# io_power.net
KiCad netlist of a schematic drawn in Altium Designer
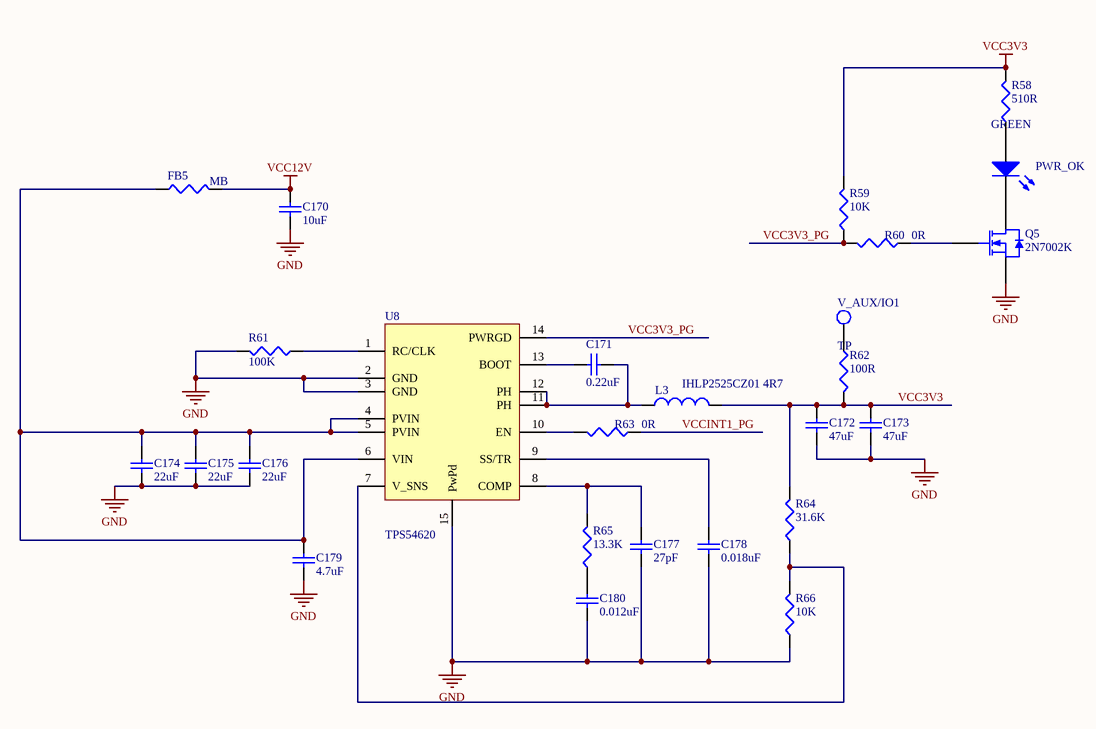
[diagram p0: io_power.SchDoc]

(export (version "E")
  (design (tool "Eeschema 10.0.6"))
  (components
    (comp (ref "C170")
      (value "10uF")
      (footprint "CAPC3216N")
      (description "Capacitor (Semiconductor SIM Model)")
      (fields (field (name "PUBLISHER") "Altium Limited"))
      (libsource (lib "Miscellaneous Devices") (part "Cap Semi"))
    )
    (comp (ref "C171")
      (value "0.22uF")
      (footprint "CAPC1608N")
      (description "Ceramic Chip Capacitor - Standard")
      (fields (field (name "PUBLISHER") "Altium Limited"))
      (libsource (lib "KEMET Chip Capacitor") (part "C0603"))
    )
    (comp (ref "C172")
      (value "47uF")
      (footprint "CAPC3225N")
      (description "Ceramic Chip Capacitor - Standard")
      (fields (field (name "PUBLISHER") "Altium Limited"))
      (libsource (lib "KEMET Chip Capacitor") (part "C1210"))
    )
    (comp (ref "C173")
      (value "47uF")
      (footprint "CAPC3225N")
      (description "Ceramic Chip Capacitor - Standard")
      (fields (field (name "PUBLISHER") "Altium Limited"))
      (libsource (lib "KEMET Chip Capacitor") (part "C1210"))
    )
    (comp (ref "C174")
      (value "22uF")
      (footprint "CAPC3225N")
      (description "Ceramic Chip Capacitor - Standard")
      (fields (field (name "PUBLISHER") "Altium Limited"))
      (libsource (lib "KEMET Chip Capacitor") (part "C1210"))
    )
    (comp (ref "C175")
      (value "22uF")
      (footprint "CAPC3225N")
      (description "Ceramic Chip Capacitor - Standard")
      (fields (field (name "PUBLISHER") "Altium Limited"))
      (libsource (lib "KEMET Chip Capacitor") (part "C1210"))
    )
    (comp (ref "C176")
      (value "22uF")
      (footprint "CAPC3225N")
      (description "Ceramic Chip Capacitor - Standard")
      (fields (field (name "PUBLISHER") "Altium Limited"))
      (libsource (lib "KEMET Chip Capacitor") (part "C1210"))
    )
    (comp (ref "C177")
      (value "27pF")
      (footprint "CAPC1608N")
      (description "Ceramic Chip Capacitor - Standard")
      (fields (field (name "PUBLISHER") "Altium Limited"))
      (libsource (lib "KEMET Chip Capacitor") (part "C0603"))
    )
    (comp (ref "C178")
      (value "0.018uF")
      (footprint "CAPC1608N")
      (description "Ceramic Chip Capacitor - Standard")
      (fields (field (name "PUBLISHER") "Altium Limited"))
      (libsource (lib "KEMET Chip Capacitor") (part "C0603"))
    )
    (comp (ref "C179")
      (value "4.7uF")
      (footprint "CAPC2012N")
      (description "Ceramic Chip Capacitor - Standard")
      (fields (field (name "PUBLISHER") "Altium Limited"))
      (libsource (lib "KEMET Chip Capacitor") (part "C0805"))
    )
    (comp (ref "C180")
      (value "0.012uF")
      (footprint "CAPC1608N")
      (description "Ceramic Chip Capacitor - Standard")
      (fields (field (name "PUBLISHER") "Altium Limited"))
      (libsource (lib "KEMET Chip Capacitor") (part "C0603"))
    )
    (comp (ref "FB5")
      (value "MB")
      (footprint "INDC3216N")
      (description "Resistor")
      (fields (field (name "PUBLISHER") "Altium Limited"))
      (libsource (lib "Miscellaneous Devices") (part "Res3"))
    )
    (comp (ref "L3")
      (value "IHLP2525CZ01")
      (footprint "IHLP2525")
      (description "Inductor")
      (fields (field (name "ALTIUM_VALUE") "4R7") (field (name "PUBLISHER") "Altium Limited"))
      (libsource (lib "S6_2") (part "Inductor"))
    )
    (comp (ref "PWR_OK")
      (value "GREEN")
      (footprint "CD1608-0603")
      (description "Typical BLUE SiC LED")
      (fields (field (name "PUBLISHER") "Altium Limited"))
      (libsource (lib "Miscellaneous Devices") (part "LED3"))
    )
    (comp (ref "Q5")
      (value "2N7002K")
      (footprint "SOT23_N")
      (description "N-channel Enhancement Mode Field-effect Transistor")
      (fields (field (name "PUBLISHER") "Altium Limited"))
      (libsource (lib "Philips Discrete MOSFET - Low Power") (part "2N7002"))
    )
    (comp (ref "R58")
      (value "510R")
      (footprint "RESC1005N")
      (description "Resistor")
      (fields (field (name "PUBLISHER") "Altium Limited"))
      (libsource (lib "Miscellaneous Devices") (part "Res3"))
    )
    (comp (ref "R59")
      (value "10K")
      (footprint "RESC1608N")
      (description "Resistor")
      (fields (field (name "PUBLISHER") "Altium Limited"))
      (libsource (lib "Miscellaneous Devices") (part "Res3"))
    )
    (comp (ref "R60")
      (value "0R")
      (footprint "RESC1005N")
      (description "Resistor")
      (fields (field (name "PUBLISHER") "Altium Limited"))
      (libsource (lib "Miscellaneous Devices") (part "Res3"))
    )
    (comp (ref "R61")
      (value "100K")
      (footprint "RESC1005N")
      (description "Resistor")
      (fields (field (name "PUBLISHER") "Altium Limited"))
      (libsource (lib "Miscellaneous Devices") (part "Res3"))
    )
    (comp (ref "R62")
      (value "100R")
      (footprint "RESC1005N")
      (description "Resistor")
      (fields (field (name "PUBLISHER") "Altium Limited"))
      (libsource (lib "Miscellaneous Devices") (part "Res3"))
    )
    (comp (ref "R63")
      (value "0R")
      (footprint "RESC1005N")
      (description "Resistor")
      (fields (field (name "PUBLISHER") "Altium Limited"))
      (libsource (lib "Miscellaneous Devices") (part "Res3"))
    )
    (comp (ref "R64")
      (value "31.6K")
      (footprint "RESC1608N")
      (description "Resistor")
      (fields (field (name "PUBLISHER") "Altium Limited"))
      (libsource (lib "Miscellaneous Devices") (part "Res3"))
    )
    (comp (ref "R65")
      (value "13.3K")
      (footprint "RESC1608N")
      (description "Resistor")
      (fields (field (name "PUBLISHER") "Altium Limited"))
      (libsource (lib "Miscellaneous Devices") (part "Res3"))
    )
    (comp (ref "R66")
      (value "10K")
      (footprint "RESC1608N")
      (description "Resistor")
      (fields (field (name "PUBLISHER") "Altium Limited"))
      (libsource (lib "Miscellaneous Devices") (part "Res3"))
    )
    (comp (ref "U8") (value "TPS54620") (footprint "VQFN-14") (libsource (lib "S6_2") (part "TPS54620")))
    (comp (ref "V_AUX/IO1") (value "TP") (footprint "PIN1") (libsource (lib "S6") (part "TP")))
  )
  (nets
    (net (code "1") (name "/VCC3V3_PG") (class "Default")
      (node (ref "R59") (pin "1") (pinfunction "1_1") (pintype "passive"))
      (node (ref "R60") (pin "2") (pinfunction "2_2") (pintype "passive"))
      (node (ref "U8") (pin "14") (pinfunction "PWRGD_14") (pintype "passive"))
    )
    (net (code "2") (name "/VCCINT1_PG") (class "Default")
      (node (ref "R63") (pin "1") (pinfunction "1_1") (pintype "passive"))
    )
    (net (code "3") (name "GND") (class "Default")
      (node (ref "C170") (pin "1") (pinfunction "1_1") (pintype "passive"))
      (node (ref "C172") (pin "1") (pinfunction "1_1") (pintype "passive"))
      (node (ref "C173") (pin "1") (pinfunction "1_1") (pintype "passive"))
      (node (ref "C174") (pin "1") (pinfunction "1_1") (pintype "passive"))
      (node (ref "C175") (pin "1") (pinfunction "1_1") (pintype "passive"))
      (node (ref "C176") (pin "1") (pinfunction "1_1") (pintype "passive"))
      (node (ref "C177") (pin "1") (pinfunction "1_1") (pintype "passive"))
      (node (ref "C178") (pin "1") (pinfunction "1_1") (pintype "passive"))
      (node (ref "C179") (pin "1") (pinfunction "1_1") (pintype "passive"))
      (node (ref "C180") (pin "1") (pinfunction "1_1") (pintype "passive"))
      (node (ref "Q5") (pin "2") (pinfunction "S_2") (pintype "passive"))
      (node (ref "R61") (pin "2") (pinfunction "2_2") (pintype "passive"))
      (node (ref "R66") (pin "1") (pinfunction "1_1") (pintype "passive"))
      (node (ref "U8") (pin "15") (pinfunction "PwPd_15") (pintype "passive"))
      (node (ref "U8") (pin "2") (pinfunction "GND_2") (pintype "passive"))
      (node (ref "U8") (pin "3") (pinfunction "GND_3") (pintype "passive"))
    )
    (net (code "4") (name "Net-(C171-Pad2)") (class "Default")
      (node (ref "C171") (pin "2") (pinfunction "2_2") (pintype "passive"))
      (node (ref "L3") (pin "1") (pinfunction "1_1") (pintype "passive"))
      (node (ref "U8") (pin "11") (pinfunction "PH_11") (pintype "passive"))
      (node (ref "U8") (pin "12") (pinfunction "PH_12") (pintype "passive"))
    )
    (net (code "5") (name "Net-(C180-Pad2)") (class "Default")
      (node (ref "C180") (pin "2") (pinfunction "2_2") (pintype "passive"))
      (node (ref "R65") (pin "1") (pinfunction "1_1") (pintype "passive"))
    )
    (net (code "6") (name "Net-(PWR_OK-A)") (class "Default")
      (node (ref "PWR_OK") (pin "1") (pinfunction "A_1") (pintype "passive"))
      (node (ref "R58") (pin "1") (pinfunction "1_1") (pintype "passive"))
    )
    (net (code "7") (name "Net-(PWR_OK-K)") (class "Default")
      (node (ref "PWR_OK") (pin "2") (pinfunction "K_2") (pintype "passive"))
      (node (ref "Q5") (pin "3") (pinfunction "D_3") (pintype "passive"))
    )
    (net (code "8") (name "Net-(Q5-G)") (class "Default")
      (node (ref "Q5") (pin "1") (pinfunction "G_1") (pintype "passive"))
      (node (ref "R60") (pin "1") (pinfunction "1_1") (pintype "passive"))
    )
    (net (code "9") (name "Net-(U8-BOOT)") (class "Default")
      (node (ref "C171") (pin "1") (pinfunction "1_1") (pintype "passive"))
      (node (ref "U8") (pin "13") (pinfunction "BOOT_13") (pintype "passive"))
    )
    (net (code "10") (name "Net-(U8-COMP)") (class "Default")
      (node (ref "C177") (pin "2") (pinfunction "2_2") (pintype "passive"))
      (node (ref "R65") (pin "2") (pinfunction "2_2") (pintype "passive"))
      (node (ref "U8") (pin "8") (pinfunction "COMP_8") (pintype "passive"))
    )
    (net (code "11") (name "Net-(U8-EN)") (class "Default")
      (node (ref "R63") (pin "2") (pinfunction "2_2") (pintype "passive"))
      (node (ref "U8") (pin "10") (pinfunction "EN_10") (pintype "passive"))
    )
    (net (code "12") (name "Net-(U8-RC{slash}CLK)") (class "Default")
      (node (ref "R61") (pin "1") (pinfunction "1_1") (pintype "passive"))
      (node (ref "U8") (pin "1") (pinfunction "RC/CLK_1") (pintype "passive"))
    )
    (net (code "13") (name "Net-(U8-SS{slash}TR)") (class "Default")
      (node (ref "C178") (pin "2") (pinfunction "2_2") (pintype "passive"))
      (node (ref "U8") (pin "9") (pinfunction "SS/TR_9") (pintype "passive"))
    )
    (net (code "14") (name "Net-(U8-VIN)") (class "Default")
      (node (ref "C174") (pin "2") (pinfunction "2_2") (pintype "passive"))
      (node (ref "C175") (pin "2") (pinfunction "2_2") (pintype "passive"))
      (node (ref "C176") (pin "2") (pinfunction "2_2") (pintype "passive"))
      (node (ref "C179") (pin "2") (pinfunction "2_2") (pintype "passive"))
      (node (ref "FB5") (pin "1") (pinfunction "1_1") (pintype "passive"))
      (node (ref "U8") (pin "4") (pinfunction "PVIN_4") (pintype "passive"))
      (node (ref "U8") (pin "5") (pinfunction "PVIN_5") (pintype "passive"))
      (node (ref "U8") (pin "6") (pinfunction "VIN_6") (pintype "passive"))
    )
    (net (code "15") (name "Net-(U8-V_SNS)") (class "Default")
      (node (ref "R64") (pin "1") (pinfunction "1_1") (pintype "passive"))
      (node (ref "R66") (pin "2") (pinfunction "2_2") (pintype "passive"))
      (node (ref "U8") (pin "7") (pinfunction "V_SNS_7") (pintype "passive"))
    )
    (net (code "16") (name "Net-(V_AUX/IO1-TP)") (class "Default")
      (node (ref "R62") (pin "1") (pinfunction "1_1") (pintype "passive"))
      (node (ref "V_AUX/IO1") (pin "1") (pinfunction "TP_1") (pintype "passive"))
    )
    (net (code "17") (name "VCC3V3") (class "Default")
      (node (ref "C172") (pin "2") (pinfunction "2_2") (pintype "passive"))
      (node (ref "C173") (pin "2") (pinfunction "2_2") (pintype "passive"))
      (node (ref "L3") (pin "2") (pinfunction "2_2") (pintype "passive"))
      (node (ref "R58") (pin "2") (pinfunction "2_2") (pintype "passive"))
      (node (ref "R59") (pin "2") (pinfunction "2_2") (pintype "passive"))
      (node (ref "R62") (pin "2") (pinfunction "2_2") (pintype "passive"))
      (node (ref "R64") (pin "2") (pinfunction "2_2") (pintype "passive"))
    )
    (net (code "18") (name "VCC12V") (class "Default")
      (node (ref "C170") (pin "2") (pinfunction "2_2") (pintype "passive"))
      (node (ref "FB5") (pin "2") (pinfunction "2_2") (pintype "passive"))
    )
  )
)
